# filter-3.net
KiCad netlist of a schematic drawn in Altium Designer
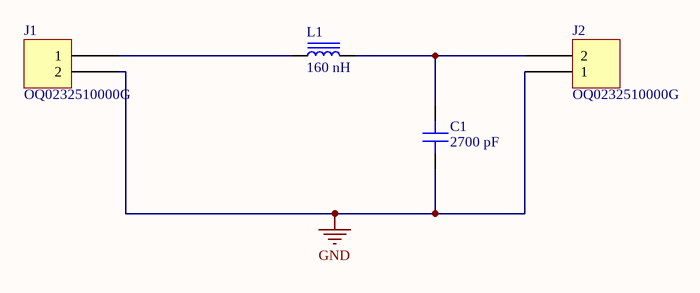
[diagram p0: filter-3.SchDoc]

(export (version "E")
  (design (tool "Eeschema 10.0.6"))
  (components
    (comp (ref "C1")
      (value "2700 pF")
      (footprint "CAP 0603_1608")
      (description "CAP CER 2700PF 25V NP0 0603")
      (fields (field (name "PART NUMBER") "C0603C272F3GAC7867") (field (name "MANUFACTURER") "KEMET"))
      (libsource (lib "Celestial Altium Library - altium_library") (part "Capacitor"))
    )
    (comp (ref "J1")
      (value "OQ0232510000G")
      (footprint "FCI 06-381-2PIN")
      (description "TERM BLOCK HDR 2POS 90DEG 3.81MM")
      (fields (field (name "MANUFACTURER") "Amphenol Anytek"))
      (libsource (lib "Celestial Altium Library - altium_library") (part "2 Pin"))
    )
    (comp (ref "J2")
      (value "OQ0232510000G")
      (footprint "FCI 06-381-2PIN")
      (description "TERM BLOCK HDR 2POS 90DEG 3.81MM")
      (fields (field (name "MANUFACTURER") "Amphenol Anytek"))
      (libsource (lib "") (part "2 Pin_1"))
    )
    (comp (ref "L1")
      (value "160 nH")
      (footprint "IND 0402_1005 RF WW")
      (description "FIXED IND 160NH 480MA 330MOHM SM")
      (fields
        (field (name "PART NUMBER") "LQW15CNR16J00D")
        (field (name "MANUFACTURER") "Murata Electronics")
      )
      (libsource (lib "Celestial Altium Library - altium_library") (part "Inductor"))
    )
  )
  (nets
    (net (code "1") (name "GND") (class "Default")
      (node (ref "C1") (pin "1") (pinfunction "1_1") (pintype "passive"))
      (node (ref "J1") (pin "2") (pinfunction "2_2") (pintype "passive"))
      (node (ref "J2") (pin "1") (pinfunction "1_1") (pintype "passive"))
    )
    (net (code "2") (name "Net-(C1-Pad2)") (class "Default")
      (node (ref "C1") (pin "2") (pinfunction "2_2") (pintype "passive"))
      (node (ref "J2") (pin "2") (pinfunction "2_2") (pintype "passive"))
      (node (ref "L1") (pin "2") (pinfunction "2_2") (pintype "passive"))
    )
    (net (code "3") (name "Net-(J1-Pad1)") (class "Default")
      (node (ref "J1") (pin "1") (pinfunction "1_1") (pintype "passive"))
      (node (ref "L1") (pin "1") (pinfunction "1_1") (pintype "passive"))
    )
  )
)
